# Top.net
KiCad netlist of a schematic drawn in Altium Designer
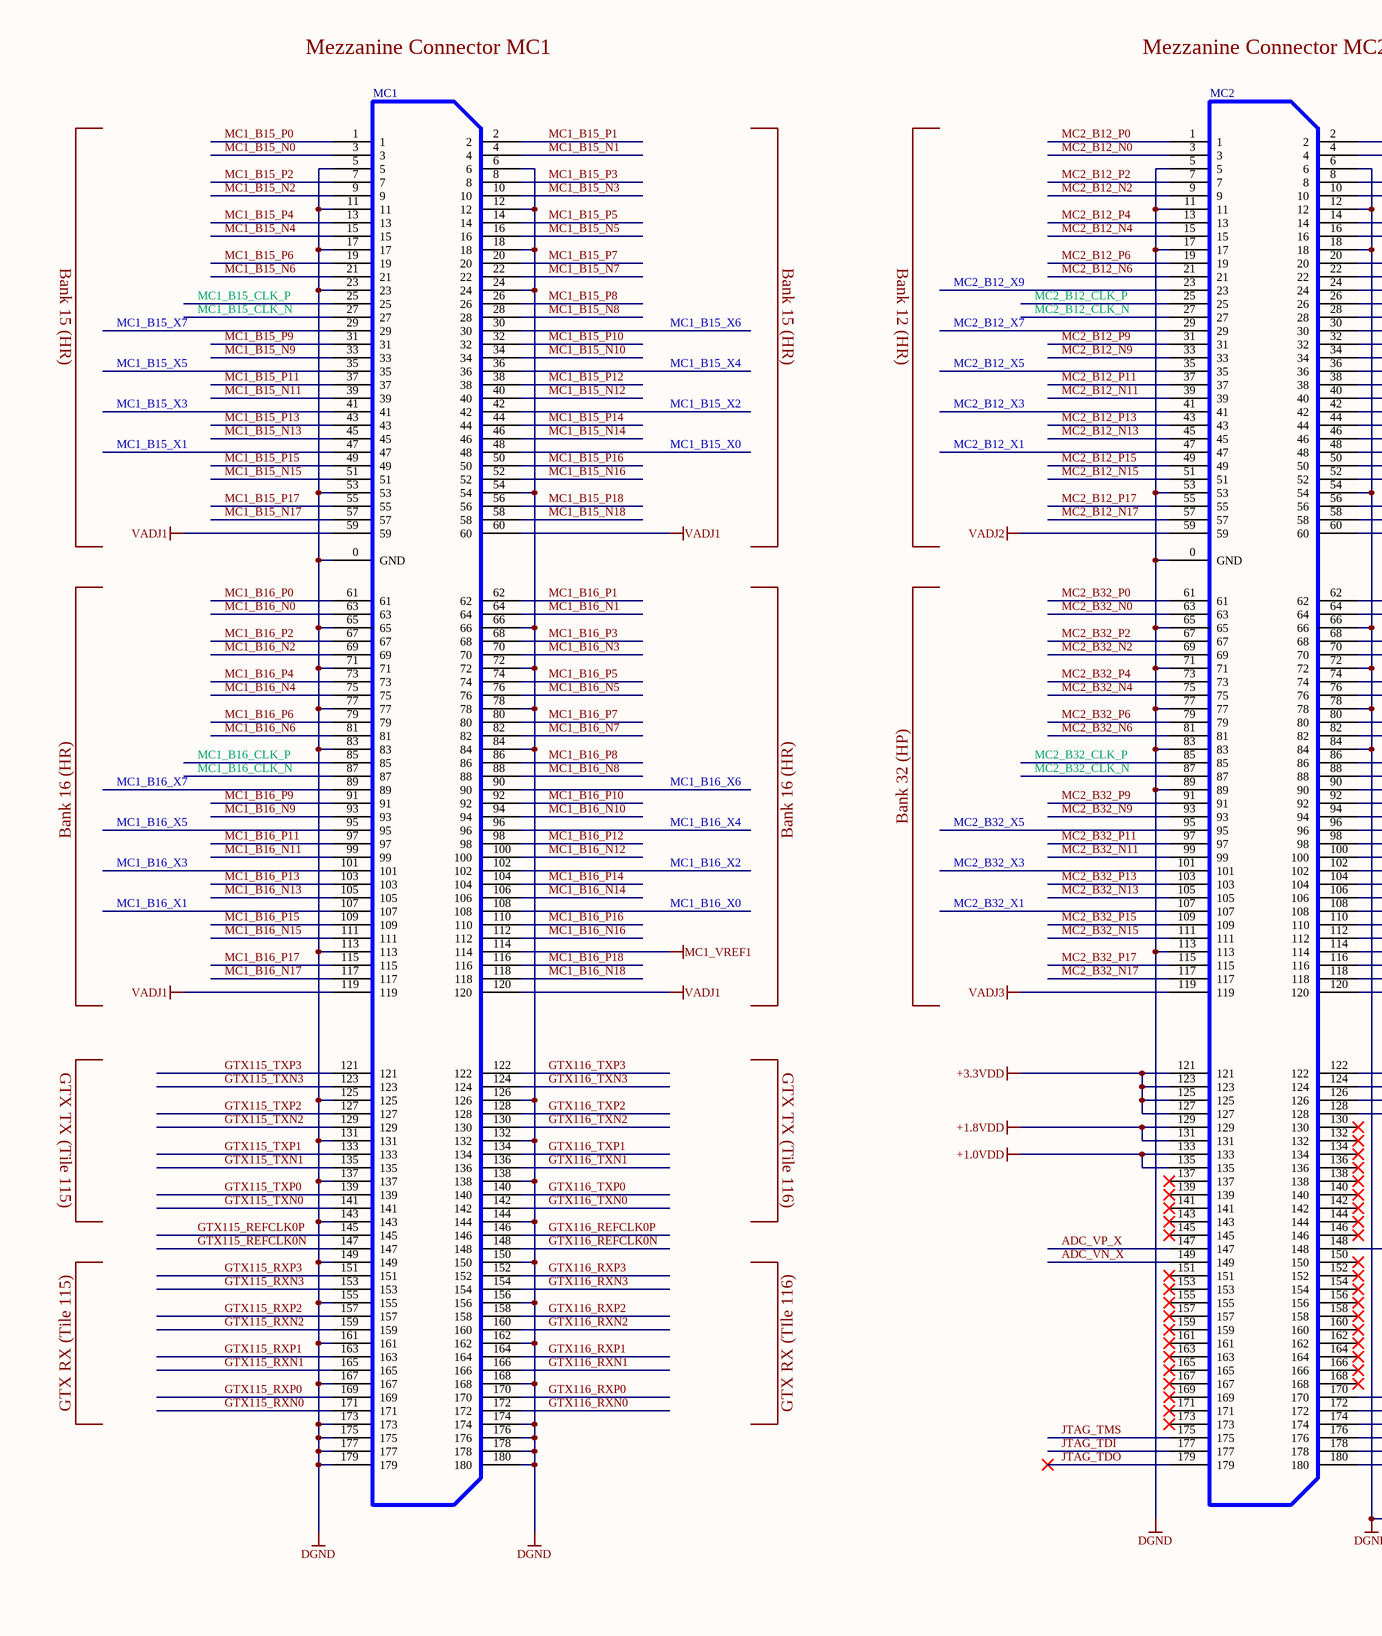
[diagram p0: Top.SchDoc, left]
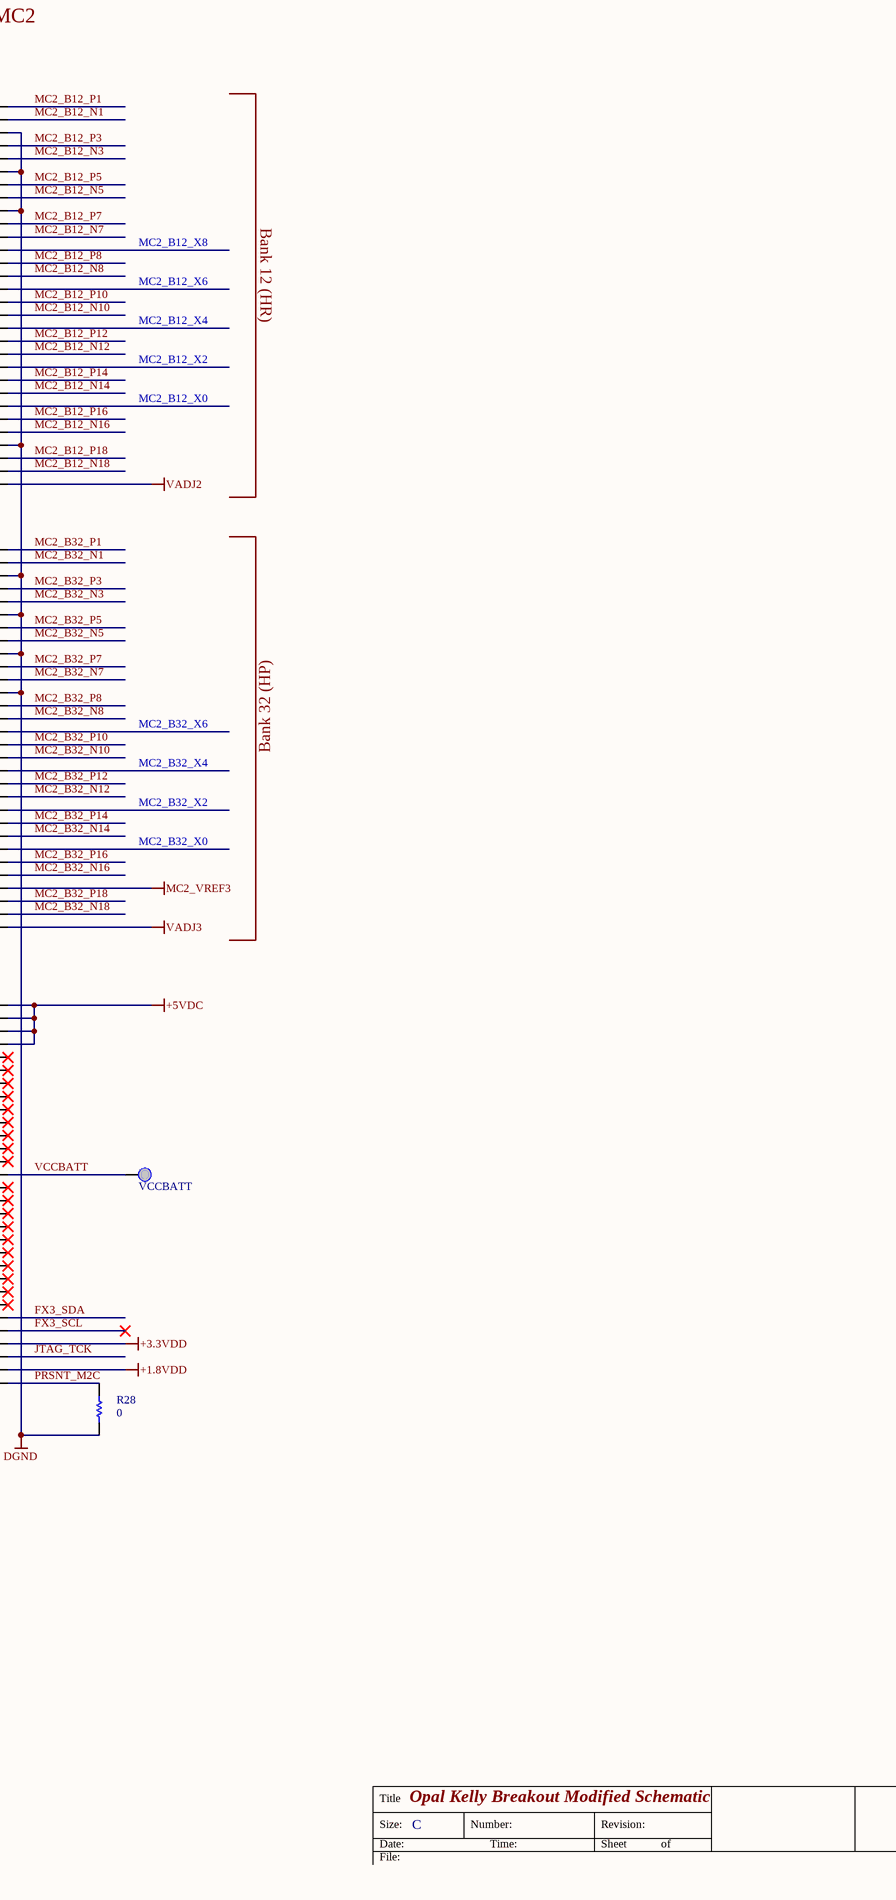
[diagram p1: Top.SchDoc, right]

(export (version "E")
  (design (tool "Eeschema 10.0.6"))
  (components
    (comp (ref "MC1")
      (value "QTH-090-01-F-D-A")
      (footprint "QTH-090-01-X-D")
      (description "0.5mm hi-speed, high-density header (Female)")
      (fields (field (name "MANUFACTURER") "Samtec") (field (name "PARTNUMBER") "000876"))
      (libsource (lib "Aligni") (part "QTH-090"))
    )
    (comp (ref "MC2")
      (value "QTH-090-01-F-D-A")
      (footprint "QTH-090-01-X-D")
      (description "0.5mm hi-speed, high-density header (Female)")
      (fields (field (name "MANUFACTURER") "Samtec") (field (name "PARTNUMBER") "000876"))
      (libsource (lib "Aligni") (part "QTH-090"))
    )
    (comp (ref "R28")
      (value "0")
      (footprint "RESC1608N")
      (description "Zero-ohm resistor")
      (fields (field (name "MANUFACTURER") "Vishay") (field (name "PARTNUMBER") "000411"))
      (libsource (lib "Aligni") (part "Resistor"))
    )
    (comp (ref "TP6")
      (value "VCCBATT")
      (footprint "TP_MED")
      (description "Testpoint")
      (fields (field (name "MANUFACTURER") "Keystone Electronics") (field (name "PARTNUMBER") "000265"))
      (libsource (lib "Aligni") (part "TESTPOINT"))
    )
  )
  (nets
    (net (code "1") (name "+1.0VDD") (class "Default")
      (node (ref "MC2") (pin "133") (pinfunction "133_133") (pintype "passive"))
      (node (ref "MC2") (pin "135") (pinfunction "135_135") (pintype "passive"))
    )
    (net (code "2") (name "+1.8VDD") (class "Default")
      (node (ref "MC2") (pin "129") (pinfunction "129_129") (pintype "passive"))
      (node (ref "MC2") (pin "131") (pinfunction "131_131") (pintype "passive"))
      (node (ref "MC2") (pin "178") (pinfunction "178_178") (pintype "passive"))
    )
    (net (code "3") (name "+3.3VDD") (class "Default")
      (node (ref "MC2") (pin "121") (pinfunction "121_121") (pintype "passive"))
      (node (ref "MC2") (pin "123") (pinfunction "123_123") (pintype "passive"))
      (node (ref "MC2") (pin "125") (pinfunction "125_125") (pintype "passive"))
      (node (ref "MC2") (pin "127") (pinfunction "127_127") (pintype "passive"))
      (node (ref "MC2") (pin "174") (pinfunction "174_174") (pintype "passive"))
    )
    (net (code "4") (name "+5VDC") (class "Default")
      (node (ref "MC2") (pin "122") (pinfunction "122_122") (pintype "passive"))
      (node (ref "MC2") (pin "124") (pinfunction "124_124") (pintype "passive"))
      (node (ref "MC2") (pin "126") (pinfunction "126_126") (pintype "passive"))
      (node (ref "MC2") (pin "128") (pinfunction "128_128") (pintype "passive"))
    )
    (net (code "5") (name "/ADC_VN_X") (class "Default")
      (node (ref "MC2") (pin "149") (pinfunction "149_149") (pintype "passive"))
    )
    (net (code "6") (name "/ADC_VP_X") (class "Default")
      (node (ref "MC2") (pin "147") (pinfunction "147_147") (pintype "passive"))
    )
    (net (code "7") (name "/FX3_SCL") (class "Default")
      (node (ref "MC2") (pin "172") (pinfunction "172_172") (pintype "passive+no_connect"))
    )
    (net (code "8") (name "/FX3_SDA") (class "Default")
      (node (ref "MC2") (pin "170") (pinfunction "170_170") (pintype "passive"))
    )
    (net (code "9") (name "/GTX115_REFCLK0N") (class "Default")
      (node (ref "MC1") (pin "147") (pinfunction "147_147") (pintype "passive"))
    )
    (net (code "10") (name "/GTX115_REFCLK0P") (class "Default")
      (node (ref "MC1") (pin "145") (pinfunction "145_145") (pintype "passive"))
    )
    (net (code "11") (name "/GTX115_RXN0") (class "Default")
      (node (ref "MC1") (pin "171") (pinfunction "171_171") (pintype "passive"))
    )
    (net (code "12") (name "/GTX115_RXN1") (class "Default")
      (node (ref "MC1") (pin "165") (pinfunction "165_165") (pintype "passive"))
    )
    (net (code "13") (name "/GTX115_RXN2") (class "Default")
      (node (ref "MC1") (pin "159") (pinfunction "159_159") (pintype "passive"))
    )
    (net (code "14") (name "/GTX115_RXN3") (class "Default")
      (node (ref "MC1") (pin "153") (pinfunction "153_153") (pintype "passive"))
    )
    (net (code "15") (name "/GTX115_RXP0") (class "Default")
      (node (ref "MC1") (pin "169") (pinfunction "169_169") (pintype "passive"))
    )
    (net (code "16") (name "/GTX115_RXP1") (class "Default")
      (node (ref "MC1") (pin "163") (pinfunction "163_163") (pintype "passive"))
    )
    (net (code "17") (name "/GTX115_RXP2") (class "Default")
      (node (ref "MC1") (pin "157") (pinfunction "157_157") (pintype "passive"))
    )
    (net (code "18") (name "/GTX115_RXP3") (class "Default")
      (node (ref "MC1") (pin "151") (pinfunction "151_151") (pintype "passive"))
    )
    (net (code "19") (name "/GTX115_TXN0") (class "Default")
      (node (ref "MC1") (pin "141") (pinfunction "141_141") (pintype "passive"))
    )
    (net (code "20") (name "/GTX115_TXN1") (class "Default")
      (node (ref "MC1") (pin "135") (pinfunction "135_135") (pintype "passive"))
    )
    (net (code "21") (name "/GTX115_TXN2") (class "Default")
      (node (ref "MC1") (pin "129") (pinfunction "129_129") (pintype "passive"))
    )
    (net (code "22") (name "/GTX115_TXN3") (class "Default")
      (node (ref "MC1") (pin "123") (pinfunction "123_123") (pintype "passive"))
    )
    (net (code "23") (name "/GTX115_TXP0") (class "Default")
      (node (ref "MC1") (pin "139") (pinfunction "139_139") (pintype "passive"))
    )
    (net (code "24") (name "/GTX115_TXP1") (class "Default")
      (node (ref "MC1") (pin "133") (pinfunction "133_133") (pintype "passive"))
    )
    (net (code "25") (name "/GTX115_TXP2") (class "Default")
      (node (ref "MC1") (pin "127") (pinfunction "127_127") (pintype "passive"))
    )
    (net (code "26") (name "/GTX115_TXP3") (class "Default")
      (node (ref "MC1") (pin "121") (pinfunction "121_121") (pintype "passive"))
    )
    (net (code "27") (name "/GTX116_REFCLK0N") (class "Default")
      (node (ref "MC1") (pin "148") (pinfunction "148_148") (pintype "passive"))
    )
    (net (code "28") (name "/GTX116_REFCLK0P") (class "Default")
      (node (ref "MC1") (pin "146") (pinfunction "146_146") (pintype "passive"))
    )
    (net (code "29") (name "/GTX116_RXN0") (class "Default")
      (node (ref "MC1") (pin "172") (pinfunction "172_172") (pintype "passive"))
    )
    (net (code "30") (name "/GTX116_RXN1") (class "Default")
      (node (ref "MC1") (pin "166") (pinfunction "166_166") (pintype "passive"))
    )
    (net (code "31") (name "/GTX116_RXN2") (class "Default")
      (node (ref "MC1") (pin "160") (pinfunction "160_160") (pintype "passive"))
    )
    (net (code "32") (name "/GTX116_RXN3") (class "Default")
      (node (ref "MC1") (pin "154") (pinfunction "154_154") (pintype "passive"))
    )
    (net (code "33") (name "/GTX116_RXP0") (class "Default")
      (node (ref "MC1") (pin "170") (pinfunction "170_170") (pintype "passive"))
    )
    (net (code "34") (name "/GTX116_RXP1") (class "Default")
      (node (ref "MC1") (pin "164") (pinfunction "164_164") (pintype "passive"))
    )
    (net (code "35") (name "/GTX116_RXP2") (class "Default")
      (node (ref "MC1") (pin "158") (pinfunction "158_158") (pintype "passive"))
    )
    (net (code "36") (name "/GTX116_RXP3") (class "Default")
      (node (ref "MC1") (pin "152") (pinfunction "152_152") (pintype "passive"))
    )
    (net (code "37") (name "/GTX116_TXN0") (class "Default")
      (node (ref "MC1") (pin "142") (pinfunction "142_142") (pintype "passive"))
    )
    (net (code "38") (name "/GTX116_TXN1") (class "Default")
      (node (ref "MC1") (pin "136") (pinfunction "136_136") (pintype "passive"))
    )
    (net (code "39") (name "/GTX116_TXN2") (class "Default")
      (node (ref "MC1") (pin "130") (pinfunction "130_130") (pintype "passive"))
    )
    (net (code "40") (name "/GTX116_TXN3") (class "Default")
      (node (ref "MC1") (pin "124") (pinfunction "124_124") (pintype "passive"))
    )
    (net (code "41") (name "/GTX116_TXP0") (class "Default")
      (node (ref "MC1") (pin "140") (pinfunction "140_140") (pintype "passive"))
    )
    (net (code "42") (name "/GTX116_TXP1") (class "Default")
      (node (ref "MC1") (pin "134") (pinfunction "134_134") (pintype "passive"))
    )
    (net (code "43") (name "/GTX116_TXP2") (class "Default")
      (node (ref "MC1") (pin "128") (pinfunction "128_128") (pintype "passive"))
    )
    (net (code "44") (name "/GTX116_TXP3") (class "Default")
      (node (ref "MC1") (pin "122") (pinfunction "122_122") (pintype "passive"))
    )
    (net (code "45") (name "/JTAG_TCK") (class "Default")
      (node (ref "MC2") (pin "176") (pinfunction "176_176") (pintype "passive"))
    )
    (net (code "46") (name "/JTAG_TDI") (class "Default")
      (node (ref "MC2") (pin "177") (pinfunction "177_177") (pintype "passive"))
    )
    (net (code "47") (name "/JTAG_TDO") (class "Default")
      (node (ref "MC2") (pin "179") (pinfunction "179_179") (pintype "passive+no_connect"))
    )
    (net (code "48") (name "/JTAG_TMS") (class "Default")
      (node (ref "MC2") (pin "175") (pinfunction "175_175") (pintype "passive"))
    )
    (net (code "49") (name "/MC1_B15_CLK_N") (class "Default")
      (node (ref "MC1") (pin "27") (pinfunction "27_27") (pintype "passive"))
    )
    (net (code "50") (name "/MC1_B15_CLK_P") (class "Default")
      (node (ref "MC1") (pin "25") (pinfunction "25_25") (pintype "passive"))
    )
    (net (code "51") (name "/MC1_B15_N0") (class "Default")
      (node (ref "MC1") (pin "3") (pinfunction "3_3") (pintype "passive"))
    )
    (net (code "52") (name "/MC1_B15_N1") (class "Default")
      (node (ref "MC1") (pin "4") (pinfunction "4_4") (pintype "passive"))
    )
    (net (code "53") (name "/MC1_B15_N2") (class "Default")
      (node (ref "MC1") (pin "9") (pinfunction "9_9") (pintype "passive"))
    )
    (net (code "54") (name "/MC1_B15_N3") (class "Default")
      (node (ref "MC1") (pin "10") (pinfunction "10_10") (pintype "passive"))
    )
    (net (code "55") (name "/MC1_B15_N4") (class "Default")
      (node (ref "MC1") (pin "15") (pinfunction "15_15") (pintype "passive"))
    )
    (net (code "56") (name "/MC1_B15_N5") (class "Default")
      (node (ref "MC1") (pin "16") (pinfunction "16_16") (pintype "passive"))
    )
    (net (code "57") (name "/MC1_B15_N6") (class "Default")
      (node (ref "MC1") (pin "21") (pinfunction "21_21") (pintype "passive"))
    )
    (net (code "58") (name "/MC1_B15_N7") (class "Default")
      (node (ref "MC1") (pin "22") (pinfunction "22_22") (pintype "passive"))
    )
    (net (code "59") (name "/MC1_B15_N8") (class "Default")
      (node (ref "MC1") (pin "28") (pinfunction "28_28") (pintype "passive"))
    )
    (net (code "60") (name "/MC1_B15_N9") (class "Default")
      (node (ref "MC1") (pin "33") (pinfunction "33_33") (pintype "passive"))
    )
    (net (code "61") (name "/MC1_B15_N10") (class "Default")
      (node (ref "MC1") (pin "34") (pinfunction "34_34") (pintype "passive"))
    )
    (net (code "62") (name "/MC1_B15_N11") (class "Default")
      (node (ref "MC1") (pin "39") (pinfunction "39_39") (pintype "passive"))
    )
    (net (code "63") (name "/MC1_B15_N12") (class "Default")
      (node (ref "MC1") (pin "40") (pinfunction "40_40") (pintype "passive"))
    )
    (net (code "64") (name "/MC1_B15_N13") (class "Default")
      (node (ref "MC1") (pin "45") (pinfunction "45_45") (pintype "passive"))
    )
    (net (code "65") (name "/MC1_B15_N14") (class "Default")
      (node (ref "MC1") (pin "46") (pinfunction "46_46") (pintype "passive"))
    )
    (net (code "66") (name "/MC1_B15_N15") (class "Default")
      (node (ref "MC1") (pin "51") (pinfunction "51_51") (pintype "passive"))
    )
    (net (code "67") (name "/MC1_B15_N16") (class "Default")
      (node (ref "MC1") (pin "52") (pinfunction "52_52") (pintype "passive"))
    )
    (net (code "68") (name "/MC1_B15_N17") (class "Default")
      (node (ref "MC1") (pin "57") (pinfunction "57_57") (pintype "passive"))
    )
    (net (code "69") (name "/MC1_B15_N18") (class "Default")
      (node (ref "MC1") (pin "58") (pinfunction "58_58") (pintype "passive"))
    )
    (net (code "70") (name "/MC1_B15_P0") (class "Default")
      (node (ref "MC1") (pin "1") (pinfunction "1_1") (pintype "passive"))
    )
    (net (code "71") (name "/MC1_B15_P1") (class "Default")
      (node (ref "MC1") (pin "2") (pinfunction "2_2") (pintype "passive"))
    )
    (net (code "72") (name "/MC1_B15_P2") (class "Default")
      (node (ref "MC1") (pin "7") (pinfunction "7_7") (pintype "passive"))
    )
    (net (code "73") (name "/MC1_B15_P3") (class "Default")
      (node (ref "MC1") (pin "8") (pinfunction "8_8") (pintype "passive"))
    )
    (net (code "74") (name "/MC1_B15_P4") (class "Default")
      (node (ref "MC1") (pin "13") (pinfunction "13_13") (pintype "passive"))
    )
    (net (code "75") (name "/MC1_B15_P5") (class "Default")
      (node (ref "MC1") (pin "14") (pinfunction "14_14") (pintype "passive"))
    )
    (net (code "76") (name "/MC1_B15_P6") (class "Default")
      (node (ref "MC1") (pin "19") (pinfunction "19_19") (pintype "passive"))
    )
    (net (code "77") (name "/MC1_B15_P7") (class "Default")
      (node (ref "MC1") (pin "20") (pinfunction "20_20") (pintype "passive"))
    )
    (net (code "78") (name "/MC1_B15_P8") (class "Default")
      (node (ref "MC1") (pin "26") (pinfunction "26_26") (pintype "passive"))
    )
    (net (code "79") (name "/MC1_B15_P9") (class "Default")
      (node (ref "MC1") (pin "31") (pinfunction "31_31") (pintype "passive"))
    )
    (net (code "80") (name "/MC1_B15_P10") (class "Default")
      (node (ref "MC1") (pin "32") (pinfunction "32_32") (pintype "passive"))
    )
    (net (code "81") (name "/MC1_B15_P11") (class "Default")
      (node (ref "MC1") (pin "37") (pinfunction "37_37") (pintype "passive"))
    )
    (net (code "82") (name "/MC1_B15_P12") (class "Default")
      (node (ref "MC1") (pin "38") (pinfunction "38_38") (pintype "passive"))
    )
    (net (code "83") (name "/MC1_B15_P13") (class "Default")
      (node (ref "MC1") (pin "43") (pinfunction "43_43") (pintype "passive"))
    )
    (net (code "84") (name "/MC1_B15_P14") (class "Default")
      (node (ref "MC1") (pin "44") (pinfunction "44_44") (pintype "passive"))
    )
    (net (code "85") (name "/MC1_B15_P15") (class "Default")
      (node (ref "MC1") (pin "49") (pinfunction "49_49") (pintype "passive"))
    )
    (net (code "86") (name "/MC1_B15_P16") (class "Default")
      (node (ref "MC1") (pin "50") (pinfunction "50_50") (pintype "passive"))
    )
    (net (code "87") (name "/MC1_B15_P17") (class "Default")
      (node (ref "MC1") (pin "55") (pinfunction "55_55") (pintype "passive"))
    )
    (net (code "88") (name "/MC1_B15_P18") (class "Default")
      (node (ref "MC1") (pin "56") (pinfunction "56_56") (pintype "passive"))
    )
    (net (code "89") (name "/MC1_B15_X0") (class "Default")
      (node (ref "MC1") (pin "48") (pinfunction "48_48") (pintype "passive"))
    )
    (net (code "90") (name "/MC1_B15_X1") (class "Default")
      (node (ref "MC1") (pin "47") (pinfunction "47_47") (pintype "passive"))
    )
    (net (code "91") (name "/MC1_B15_X2") (class "Default")
      (node (ref "MC1") (pin "42") (pinfunction "42_42") (pintype "passive"))
    )
    (net (code "92") (name "/MC1_B15_X3") (class "Default")
      (node (ref "MC1") (pin "41") (pinfunction "41_41") (pintype "passive"))
    )
    (net (code "93") (name "/MC1_B15_X4") (class "Default")
      (node (ref "MC1") (pin "36") (pinfunction "36_36") (pintype "passive"))
    )
    (net (code "94") (name "/MC1_B15_X5") (class "Default")
      (node (ref "MC1") (pin "35") (pinfunction "35_35") (pintype "passive"))
    )
    (net (code "95") (name "/MC1_B15_X6") (class "Default")
      (node (ref "MC1") (pin "30") (pinfunction "30_30") (pintype "passive"))
    )
    (net (code "96") (name "/MC1_B15_X7") (class "Default")
      (node (ref "MC1") (pin "29") (pinfunction "29_29") (pintype "passive"))
    )
    (net (code "97") (name "/MC1_B16_CLK_N") (class "Default")
      (node (ref "MC1") (pin "87") (pinfunction "87_87") (pintype "passive"))
    )
    (net (code "98") (name "/MC1_B16_CLK_P") (class "Default")
      (node (ref "MC1") (pin "85") (pinfunction "85_85") (pintype "passive"))
    )
    (net (code "99") (name "/MC1_B16_N0") (class "Default")
      (node (ref "MC1") (pin "63") (pinfunction "63_63") (pintype "passive"))
    )
    (net (code "100") (name "/MC1_B16_N1") (class "Default")
      (node (ref "MC1") (pin "64") (pinfunction "64_64") (pintype "passive"))
    )
    (net (code "101") (name "/MC1_B16_N2") (class "Default")
      (node (ref "MC1") (pin "69") (pinfunction "69_69") (pintype "passive"))
    )
    (net (code "102") (name "/MC1_B16_N3") (class "Default")
      (node (ref "MC1") (pin "70") (pinfunction "70_70") (pintype "passive"))
    )
    (net (code "103") (name "/MC1_B16_N4") (class "Default")
      (node (ref "MC1") (pin "75") (pinfunction "75_75") (pintype "passive"))
    )
    (net (code "104") (name "/MC1_B16_N5") (class "Default")
      (node (ref "MC1") (pin "76") (pinfunction "76_76") (pintype "passive"))
    )
    (net (code "105") (name "/MC1_B16_N6") (class "Default")
      (node (ref "MC1") (pin "81") (pinfunction "81_81") (pintype "passive"))
    )
    (net (code "106") (name "/MC1_B16_N7") (class "Default")
      (node (ref "MC1") (pin "82") (pinfunction "82_82") (pintype "passive"))
    )
    (net (code "107") (name "/MC1_B16_N8") (class "Default")
      (node (ref "MC1") (pin "88") (pinfunction "88_88") (pintype "passive"))
    )
    (net (code "108") (name "/MC1_B16_N9") (class "Default")
      (node (ref "MC1") (pin "93") (pinfunction "93_93") (pintype "passive"))
    )
    (net (code "109") (name "/MC1_B16_N10") (class "Default")
      (node (ref "MC1") (pin "94") (pinfunction "94_94") (pintype "passive"))
    )
    (net (code "110") (name "/MC1_B16_N11") (class "Default")
      (node (ref "MC1") (pin "99") (pinfunction "99_99") (pintype "passive"))
    )
    (net (code "111") (name "/MC1_B16_N12") (class "Default")
      (node (ref "MC1") (pin "100") (pinfunction "100_100") (pintype "passive"))
    )
    (net (code "112") (name "/MC1_B16_N13") (class "Default")
      (node (ref "MC1") (pin "105") (pinfunction "105_105") (pintype "passive"))
    )
    (net (code "113") (name "/MC1_B16_N14") (class "Default")
      (node (ref "MC1") (pin "106") (pinfunction "106_106") (pintype "passive"))
    )
    (net (code "114") (name "/MC1_B16_N15") (class "Default")
      (node (ref "MC1") (pin "111") (pinfunction "111_111") (pintype "passive"))
    )
    (net (code "115") (name "/MC1_B16_N16") (class "Default")
      (node (ref "MC1") (pin "112") (pinfunction "112_112") (pintype "passive"))
    )
    (net (code "116") (name "/MC1_B16_N17") (class "Default")
      (node (ref "MC1") (pin "117") (pinfunction "117_117") (pintype "passive"))
    )
    (net (code "117") (name "/MC1_B16_N18") (class "Default")
      (node (ref "MC1") (pin "118") (pinfunction "118_118") (pintype "passive"))
    )
    (net (code "118") (name "/MC1_B16_P0") (class "Default")
      (node (ref "MC1") (pin "61") (pinfunction "61_61") (pintype "passive"))
    )
    (net (code "119") (name "/MC1_B16_P1") (class "Default")
      (node (ref "MC1") (pin "62") (pinfunction "62_62") (pintype "passive"))
    )
    (net (code "120") (name "/MC1_B16_P2") (class "Default")
      (node (ref "MC1") (pin "67") (pinfunction "67_67") (pintype "passive"))
    )
    (net (code "121") (name "/MC1_B16_P3") (class "Default")
      (node (ref "MC1") (pin "68") (pinfunction "68_68") (pintype "passive"))
    )
    (net (code "122") (name "/MC1_B16_P4") (class "Default")
      (node (ref "MC1") (pin "73") (pinfunction "73_73") (pintype "passive"))
    )
    (net (code "123") (name "/MC1_B16_P5") (class "Default")
      (node (ref "MC1") (pin "74") (pinfunction "74_74") (pintype "passive"))
    )
    (net (code "124") (name "/MC1_B16_P6") (class "Default")
      (node (ref "MC1") (pin "79") (pinfunction "79_79") (pintype "passive"))
    )
    (net (code "125") (name "/MC1_B16_P7") (class "Default")
      (node (ref "MC1") (pin "80") (pinfunction "80_80") (pintype "passive"))
    )
    (net (code "126") (name "/MC1_B16_P8") (class "Default")
      (node (ref "MC1") (pin "86") (pinfunction "86_86") (pintype "passive"))
    )
    (net (code "127") (name "/MC1_B16_P9") (class "Default")
      (node (ref "MC1") (pin "91") (pinfunction "91_91") (pintype "passive"))
    )
    (net (code "128") (name "/MC1_B16_P10") (class "Default")
      (node (ref "MC1") (pin "92") (pinfunction "92_92") (pintype "passive"))
    )
    (net (code "129") (name "/MC1_B16_P11") (class "Default")
      (node (ref "MC1") (pin "97") (pinfunction "97_97") (pintype "passive"))
    )
    (net (code "130") (name "/MC1_B16_P12") (class "Default")
      (node (ref "MC1") (pin "98") (pinfunction "98_98") (pintype "passive"))
    )
    (net (code "131") (name "/MC1_B16_P13") (class "Default")
      (node (ref "MC1") (pin "103") (pinfunction "103_103") (pintype "passive"))
    )
    (net (code "132") (name "/MC1_B16_P14") (class "Default")
      (node (ref "MC1") (pin "104") (pinfunction "104_104") (pintype "passive"))
    )
    (net (code "133") (name "/MC1_B16_P15") (class "Default")
      (node (ref "MC1") (pin "109") (pinfunction "109_109") (pintype "passive"))
    )
    (net (code "134") (name "/MC1_B16_P16") (class "Default")
      (node (ref "MC1") (pin "110") (pinfunction "110_110") (pintype "passive"))
    )
    (net (code "135") (name "/MC1_B16_P17") (class "Default")
      (node (ref "MC1") (pin "115") (pinfunction "115_115") (pintype "passive"))
    )
    (net (code "136") (name "/MC1_B16_P18") (class "Default")
      (node (ref "MC1") (pin "116") (pinfunction "116_116") (pintype "passive"))
    )
    (net (code "137") (name "/MC1_B16_X0") (class "Default")
      (node (ref "MC1") (pin "108") (pinfunction "108_108") (pintype "passive"))
    )
    (net (code "138") (name "/MC1_B16_X1") (class "Default")
      (node (ref "MC1") (pin "107") (pinfunction "107_107") (pintype "passive"))
    )
    (net (code "139") (name "/MC1_B16_X2") (class "Default")
      (node (ref "MC1") (pin "102") (pinfunction "102_102") (pintype "passive"))
    )
    (net (code "140") (name "/MC1_B16_X3") (class "Default")
      (node (ref "MC1") (pin "101") (pinfunction "101_101") (pintype "passive"))
    )
    (net (code "141") (name "/MC1_B16_X4") (class "Default")
      (node (ref "MC1") (pin "96") (pinfunction "96_96") (pintype "passive"))
    )
    (net (code "142") (name "/MC1_B16_X5") (class "Default")
      (node (ref "MC1") (pin "95") (pinfunction "95_95") (pintype "passive"))
    )
    (net (code "143") (name "/MC1_B16_X6") (class "Default")
      (node (ref "MC1") (pin "90") (pinfunction "90_90") (pintype "passive"))
    )
    (net (code "144") (name "/MC1_B16_X7") (class "Default")
      (node (ref "MC1") (pin "89") (pinfunction "89_89") (pintype "passive"))
    )
    (net (code "145") (name "/MC2_B12_CLK_N") (class "Default")
      (node (ref "MC2") (pin "27") (pinfunction "27_27") (pintype "passive"))
    )
    (net (code "146") (name "/MC2_B12_CLK_P") (class "Default")
      (node (ref "MC2") (pin "25") (pinfunction "25_25") (pintype "passive"))
    )
    (net (code "147") (name "/MC2_B12_N0") (class "Default")
      (node (ref "MC2") (pin "3") (pinfunction "3_3") (pintype "passive"))
    )
    (net (code "148") (name "/MC2_B12_N1") (class "Default")
      (node (ref "MC2") (pin "4") (pinfunction "4_4") (pintype "passive"))
    )
    (net (code "149") (name "/MC2_B12_N2") (class "Default")
      (node (ref "MC2") (pin "9") (pinfunction "9_9") (pintype "passive"))
    )
    (net (code "150") (name "/MC2_B12_N3") (class "Default")
      (node (ref "MC2") (pin "10") (pinfunction "10_10") (pintype "passive"))
    )
    (net (code "151") (name "/MC2_B12_N4") (class "Default")
      (node (ref "MC2") (pin "15") (pinfunction "15_15") (pintype "passive"))
    )
    (net (code "152") (name "/MC2_B12_N5") (class "Default")
      (node (ref "MC2") (pin "16") (pinfunction "16_16") (pintype "passive"))
    )
    (net (code "153") (name "/MC2_B12_N6") (class "Default")
      (node (ref "MC2") (pin "21") (pinfunction "21_21") (pintype "passive"))
    )
    (net (code "154") (name "/MC2_B12_N7") (class "Default")
      (node (ref "MC2") (pin "22") (pinfunction "22_22") (pintype "passive"))
    )
    (net (code "155") (name "/MC2_B12_N8") (class "Default")
      (node (ref "MC2") (pin "28") (pinfunction "28_28") (pintype "passive"))
    )
    (net (code "156") (name "/MC2_B12_N9") (class "Default")
      (node (ref "MC2") (pin "33") (pinfunction "33_33") (pintype "passive"))
    )
    (net (code "157") (name "/MC2_B12_N10") (class "Default")
      (node (ref "MC2") (pin "34") (pinfunction "34_34") (pintype "passive"))
    )
    (net (code "158") (name "/MC2_B12_N11") (class "Default")
      (node (ref "MC2") (pin "39") (pinfunction "39_39") (pintype "passive"))
    )
    (net (code "159") (name "/MC2_B12_N12") (class "Default")
      (node (ref "MC2") (pin "40") (pinfunction "40_40") (pintype "passive"))
    )
    (net (code "160") (name "/MC2_B12_N13") (class "Default")
      (node (ref "MC2") (pin "45") (pinfunction "45_45") (pintype "passive"))
    )
    (net (code "161") (name "/MC2_B12_N14") (class "Default")
      (node (ref "MC2") (pin "46") (pinfunction "46_46") (pintype "passive"))
    )
    (net (code "162") (name "/MC2_B12_N15") (class "Default")
      (node (ref "MC2") (pin "51") (pinfunction "51_51") (pintype "passive"))
    )
    (net (code "163") (name "/MC2_B12_N16") (class "Default")
      (node (ref "MC2") (pin "52") (pinfunction "52_52") (pintype "passive"))
    )
    (net (code "164") (name "/MC2_B12_N17") (class "Default")
      (node (ref "MC2") (pin "57") (pinfunction "57_57") (pintype "passive"))
    )
    (net (code "165") (name "/MC2_B12_N18") (class "Default")
      (node (ref "MC2") (pin "58") (pinfunction "58_58") (pintype "passive"))
    )
    (net (code "166") (name "/MC2_B12_P0") (class "Default")
      (node (ref "MC2") (pin "1") (pinfunction "1_1") (pintype "passive"))
    )
    (net (code "167") (name "/MC2_B12_P1") (class "Default")
      (node (ref "MC2") (pin "2") (pinfunction "2_2") (pintype "passive"))
    )
    (net (code "168") (name "/MC2_B12_P2") (class "Default")
      (node (ref "MC2") (pin "7") (pinfunction "7_7") (pintype "passive"))
    )
    (net (code "169") (name "/MC2_B12_P3") (class "Default")
      (node (ref "MC2") (pin "8") (pinfunction "8_8") (pintype "passive"))
    )
    (net (code "170") (name "/MC2_B12_P4") (class "Default")
      (node (ref "MC2") (pin "13") (pinfunction "13_13") (pintype "passive"))
    )
    (net (code "171") (name "/MC2_B12_P5") (class "Default")
      (node (ref "MC2") (pin "14") (pinfunction "14_14") (pintype "passive"))
    )
    (net (code "172") (name "/MC2_B12_P6") (class "Default")
      (node (ref "MC2") (pin "19") (pinfunction "19_19") (pintype "passive"))
    )
    (net (code "173") (name "/MC2_B12_P7") (class "Default")
      (node (ref "MC2") (pin "20") (pinfunction "20_20") (pintype "passive"))
    )
    (net (code "174") (name "/MC2_B12_P8") (class "Default")
      (node (ref "MC2") (pin "26") (pinfunction "26_26") (pintype "passive"))
    )
    (net (code "175") (name "/MC2_B12_P9") (class "Default")
      (node (ref "MC2") (pin "31") (pinfunction "31_31") (pintype "passive"))
    )
    (net (code "176") (name "/MC2_B12_P10") (class "Default")
      (node (ref "MC2") (pin "32") (pinfunction "32_32") (pintype "passive"))
    )
    (net (code "177") (name "/MC2_B12_P11") (class "Default")
      (node (ref "MC2") (pin "37") (pinfunction "37_37") (pintype "passive"))
    )
    (net (code "178") (name "/MC2_B12_P12") (class "Default")
      (node (ref "MC2") (pin "38") (pinfunction "38_38") (pintype "passive"))
    )
    (net (code "179") (name "/MC2_B12_P13") (class "Default")
      (node (ref "MC2") (pin "43") (pinfunction "43_43") (pintype "passive"))
    )
    (net (code "180") (name "/MC2_B12_P14") (class "Default")
      (node (ref "MC2") (pin "44") (pinfunction "44_44") (pintype "passive"))
    )
    (net (code "181") (name "/MC2_B12_P15") (class "Default")
      (node (ref "MC2") (pin "49") (pinfunction "49_49") (pintype "passive"))
    )
    (net (code "182") (name "/MC2_B12_P16") (class "Default")
      (node (ref "MC2") (pin "50") (pinfunction "50_50") (pintype "passive"))
    )
    (net (code "183") (name "/MC2_B12_P17") (class "Default")
      (node (ref "MC2") (pin "55") (pinfunction "55_55") (pintype "passive"))
    )
    (net (code "184") (name "/MC2_B12_P18") (class "Default")
      (node (ref "MC2") (pin "56") (pinfunction "56_56") (pintype "passive"))
    )
    (net (code "185") (name "/MC2_B12_X0") (class "Default")
      (node (ref "MC2") (pin "48") (pinfunction "48_48") (pintype "passive"))
    )
    (net (code "186") (name "/MC2_B12_X1") (class "Default")
      (node (ref "MC2") (pin "47") (pinfunction "47_47") (pintype "passive"))
    )
    (net (code "187") (name "/MC2_B12_X2") (class "Default")
      (node (ref "MC2") (pin "42") (pinfunction "42_42") (pintype "passive"))
    )
    (net (code "188") (name "/MC2_B12_X3") (class "Default")
      (node (ref "MC2") (pin "41") (pinfunction "41_41") (pintype "passive"))
    )
    (net (code "189") (name "/MC2_B12_X4") (class "Default")
      (node (ref "MC2") (pin "36") (pinfunction "36_36") (pintype "passive"))
    )
    (net (code "190") (name "/MC2_B12_X5") (class "Default")
      (node (ref "MC2") (pin "35") (pinfunction "35_35") (pintype "passive"))
    )
    (net (code "191") (name "/MC2_B12_X6") (class "Default")
      (node (ref "MC2") (pin "30") (pinfunction "30_30") (pintype "passive"))
    )
    (net (code "192") (name "/MC2_B12_X7") (class "Default")
      (node (ref "MC2") (pin "29") (pinfunction "29_29") (pintype "passive"))
    )
    (net (code "193") (name "/MC2_B12_X8") (class "Default")
      (node (ref "MC2") (pin "24") (pinfunction "24_24") (pintype "passive"))
    )
    (net (code "194") (name "/MC2_B12_X9") (class "Default")
      (node (ref "MC2") (pin "23") (pinfunction "23_23") (pintype "passive"))
    )
    (net (code "195") (name "/MC2_B32_CLK_N") (class "Default")
      (node (ref "MC2") (pin "87") (pinfunction "87_87") (pintype "passive"))
    )
    (net (code "196") (name "/MC2_B32_CLK_P") (class "Default")
      (node (ref "MC2") (pin "85") (pinfunction "85_85") (pintype "passive"))
    )
    (net (code "197") (name "/MC2_B32_N0") (class "Default")
      (node (ref "MC2") (pin "63") (pinfunction "63_63") (pintype "passive"))
    )
    (net (code "198") (name "/MC2_B32_N1") (class "Default")
      (node (ref "MC2") (pin "64") (pinfunction "64_64") (pintype "passive"))
    )
    (net (code "199") (name "/MC2_B32_N2") (class "Default")
      (node (ref "MC2") (pin "69") (pinfunction "69_69") (pintype "passive"))
    )
    (net (code "200") (name "/MC2_B32_N3") (class "Default")
      (node (ref "MC2") (pin "70") (pinfunction "70_70") (pintype "passive"))
    )
    (net (code "201") (name "/MC2_B32_N4") (class "Default")
      (node (ref "MC2") (pin "75") (pinfunction "75_75") (pintype "passive"))
    )
    (net (code "202") (name "/MC2_B32_N5") (class "Default")
      (node (ref "MC2") (pin "76") (pinfunction "76_76") (pintype "passive"))
    )
    (net (code "203") (name "/MC2_B32_N6") (class "Default")
      (node (ref "MC2") (pin "81") (pinfunction "81_81") (pintype "passive"))
    )
    (net (code "204") (name "/MC2_B32_N7") (class "Default")
      (node (ref "MC2") (pin "82") (pinfunction "82_82") (pintype "passive"))
    )
    (net (code "205") (name "/MC2_B32_N8") (class "Default")
      (node (ref "MC2") (pin "88") (pinfunction "88_88") (pintype "passive"))
    )
    (net (code "206") (name "/MC2_B32_N9") (class "Default")
      (node (ref "MC2") (pin "93") (pinfunction "93_93") (pintype "passive"))
    )
    (net (code "207") (name "/MC2_B32_N10") (class "Default")
      (node (ref "MC2") (pin "94") (pinfunction "94_94") (pintype "passive"))
    )
    (net (code "208") (name "/MC2_B32_N11") (class "Default")
      (node (ref "MC2") (pin "99") (pinfunction "99_99") (pintype "passive"))
    )
    (net (code "209") (name "/MC2_B32_N12") (class "Default")
      (node (ref "MC2") (pin "100") (pinfunction "100_100") (pintype "passive"))
    )
    (net (code "210") (name "/MC2_B32_N13") (class "Default")
      (node (ref "MC2") (pin "105") (pinfunction "105_105") (pintype "passive"))
    )
    (net (code "211") (name "/MC2_B32_N14") (class "Default")
      (node (ref "MC2") (pin "106") (pinfunction "106_106") (pintype "passive"))
    )
    (net (code "212") (name "/MC2_B32_N15") (class "Default")
      (node (ref "MC2") (pin "111") (pinfunction "111_111") (pintype "passive"))
    )
    (net (code "213") (name "/MC2_B32_N16") (class "Default")
      (node (ref "MC2") (pin "112") (pinfunction "112_112") (pintype "passive"))
    )
    (net (code "214") (name "/MC2_B32_N17") (class "Default")
      (node (ref "MC2") (pin "117") (pinfunction "117_117") (pintype "passive"))
    )
    (net (code "215") (name "/MC2_B32_N18") (class "Default")
      (node (ref "MC2") (pin "118") (pinfunction "118_118") (pintype "passive"))
    )
    (net (code "216") (name "/MC2_B32_P0") (class "Default")
      (node (ref "MC2") (pin "61") (pinfunction "61_61") (pintype "passive"))
    )
    (net (code "217") (name "/MC2_B32_P1") (class "Default")
      (node (ref "MC2") (pin "62") (pinfunction "62_62") (pintype "passive"))
    )
    (net (code "218") (name "/MC2_B32_P2") (class "Default")
      (node (ref "MC2") (pin "67") (pinfunction "67_67") (pintype "passive"))
    )
    (net (code "219") (name "/MC2_B32_P3") (class "Default")
      (node (ref "MC2") (pin "68") (pinfunction "68_68") (pintype "passive"))
    )
    (net (code "220") (name "/MC2_B32_P4") (class "Default")
      (node (ref "MC2") (pin "73") (pinfunction "73_73") (pintype "passive"))
    )
    (net (code "221") (name "/MC2_B32_P5") (class "Default")
      (node (ref "MC2") (pin "74") (pinfunction "74_74") (pintype "passive"))
    )
    (net (code "222") (name "/MC2_B32_P6") (class "Default")
      (node (ref "MC2") (pin "79") (pinfunction "79_79") (pintype "passive"))
    )
    (net (code "223") (name "/MC2_B32_P7") (class "Default")
      (node (ref "MC2") (pin "80") (pinfunction "80_80") (pintype "passive"))
    )
    (net (code "224") (name "/MC2_B32_P8") (class "Default")
      (node (ref "MC2") (pin "86") (pinfunction "86_86") (pintype "passive"))
    )
    (net (code "225") (name "/MC2_B32_P9") (class "Default")
      (node (ref "MC2") (pin "91") (pinfunction "91_91") (pintype "passive"))
    )
    (net (code "226") (name "/MC2_B32_P10") (class "Default")
      (node (ref "MC2") (pin "92") (pinfunction "92_92") (pintype "passive"))
    )
    (net (code "227") (name "/MC2_B32_P11") (class "Default")
      (node (ref "MC2") (pin "97") (pinfunction "97_97") (pintype "passive"))
    )
    (net (code "228") (name "/MC2_B32_P12") (class "Default")
      (node (ref "MC2") (pin "98") (pinfunction "98_98") (pintype "passive"))
    )
    (net (code "229") (name "/MC2_B32_P13") (class "Default")
      (node (ref "MC2") (pin "103") (pinfunction "103_103") (pintype "passive"))
    )
    (net (code "230") (name "/MC2_B32_P14") (class "Default")
      (node (ref "MC2") (pin "104") (pinfunction "104_104") (pintype "passive"))
    )
    (net (code "231") (name "/MC2_B32_P15") (class "Default")
      (node (ref "MC2") (pin "109") (pinfunction "109_109") (pintype "passive"))
    )
    (net (code "232") (name "/MC2_B32_P16") (class "Default")
      (node (ref "MC2") (pin "110") (pinfunction "110_110") (pintype "passive"))
    )
    (net (code "233") (name "/MC2_B32_P17") (class "Default")
      (node (ref "MC2") (pin "115") (pinfunction "115_115") (pintype "passive"))
    )
    (net (code "234") (name "/MC2_B32_P18") (class "Default")
      (node (ref "MC2") (pin "116") (pinfunction "116_116") (pintype "passive"))
    )
    (net (code "235") (name "/MC2_B32_X0") (class "Default")
      (node (ref "MC2") (pin "108") (pinfunction "108_108") (pintype "passive"))
    )
    (net (code "236") (name "/MC2_B32_X1") (class "Default")
      (node (ref "MC2") (pin "107") (pinfunction "107_107") (pintype "passive"))
    )
    (net (code "237") (name "/MC2_B32_X2") (class "Default")
      (node (ref "MC2") (pin "102") (pinfunction "102_102") (pintype "passive"))
    )
    (net (code "238") (name "/MC2_B32_X3") (class "Default")
      (node (ref "MC2") (pin "101") (pinfunction "101_101") (pintype "passive"))
    )
    (net (code "239") (name "/MC2_B32_X4") (class "Default")
      (node (ref "MC2") (pin "96") (pinfunction "96_96") (pintype "passive"))
    )
    (net (code "240") (name "/MC2_B32_X5") (class "Default")
      (node (ref "MC2") (pin "95") (pinfunction "95_95") (pintype "passive"))
    )
    (net (code "241") (name "/MC2_B32_X6") (class "Default")
      (node (ref "MC2") (pin "90") (pinfunction "90_90") (pintype "passive"))
    )
    (net (code "242") (name "/PRSNT_M2C") (class "Default")
      (node (ref "MC2") (pin "180") (pinfunction "180_180") (pintype "passive"))
      (node (ref "R28") (pin "2") (pinfunction "2_2") (pintype "passive"))
    )
    (net (code "243") (name "/VCCBATT") (class "Default")
      (node (ref "MC2") (pin "148") (pinfunction "148_148") (pintype "passive"))
      (node (ref "TP6") (pin "1") (pinfunction "PIN_1") (pintype "passive"))
    )
    (net (code "244") (name "DGND") (class "Default")
      (node (ref "MC1") (pin "0") (pinfunction "GND_0") (pintype "power_in"))
      (node (ref "MC1") (pin "11") (pinfunction "11_11") (pintype "passive"))
      (node (ref "MC1") (pin "113") (pinfunction "113_113") (pintype "passive"))
      (node (ref "MC1") (pin "12") (pinfunction "12_12") (pintype "passive"))
      (node (ref "MC1") (pin "125") (pinfunction "125_125") (pintype "passive"))
      (node (ref "MC1") (pin "126") (pinfunction "126_126") (pintype "passive"))
      (node (ref "MC1") (pin "131") (pinfunction "131_131") (pintype "passive"))
      (node (ref "MC1") (pin "132") (pinfunction "132_132") (pintype "passive"))
      (node (ref "MC1") (pin "137") (pinfunction "137_137") (pintype "passive"))
      (node (ref "MC1") (pin "138") (pinfunction "138_138") (pintype "passive"))
      (node (ref "MC1") (pin "143") (pinfunction "143_143") (pintype "passive"))
      (node (ref "MC1") (pin "144") (pinfunction "144_144") (pintype "passive"))
      (node (ref "MC1") (pin "149") (pinfunction "149_149") (pintype "passive"))
      (node (ref "MC1") (pin "150") (pinfunction "150_150") (pintype "passive"))
      (node (ref "MC1") (pin "155") (pinfunction "155_155") (pintype "passive"))
      (node (ref "MC1") (pin "156") (pinfunction "156_156") (pintype "passive"))
      (node (ref "MC1") (pin "161") (pinfunction "161_161") (pintype "passive"))
      (node (ref "MC1") (pin "162") (pinfunction "162_162") (pintype "passive"))
      (node (ref "MC1") (pin "167") (pinfunction "167_167") (pintype "passive"))
      (node (ref "MC1") (pin "168") (pinfunction "168_168") (pintype "passive"))
      (node (ref "MC1") (pin "17") (pinfunction "17_17") (pintype "passive"))
      (node (ref "MC1") (pin "173") (pinfunction "173_173") (pintype "passive"))
      (node (ref "MC1") (pin "174") (pinfunction "174_174") (pintype "passive"))
      (node (ref "MC1") (pin "175") (pinfunction "175_175") (pintype "passive"))
      (node (ref "MC1") (pin "176") (pinfunction "176_176") (pintype "passive"))
      (node (ref "MC1") (pin "177") (pinfunction "177_177") (pintype "passive"))
      (node (ref "MC1") (pin "178") (pinfunction "178_178") (pintype "passive"))
      (node (ref "MC1") (pin "179") (pinfunction "179_179") (pintype "passive"))
      (node (ref "MC1") (pin "18") (pinfunction "18_18") (pintype "passive"))
      (node (ref "MC1") (pin "180") (pinfunction "180_180") (pintype "passive"))
      (node (ref "MC1") (pin "23") (pinfunction "23_23") (pintype "passive"))
      (node (ref "MC1") (pin "24") (pinfunction "24_24") (pintype "passive"))
      (node (ref "MC1") (pin "5") (pinfunction "5_5") (pintype "passive"))
      (node (ref "MC1") (pin "53") (pinfunction "53_53") (pintype "passive"))
      (node (ref "MC1") (pin "54") (pinfunction "54_54") (pintype "passive"))
      (node (ref "MC1") (pin "6") (pinfunction "6_6") (pintype "passive"))
      (node (ref "MC1") (pin "65") (pinfunction "65_65") (pintype "passive"))
      (node (ref "MC1") (pin "66") (pinfunction "66_66") (pintype "passive"))
      (node (ref "MC1") (pin "71") (pinfunction "71_71") (pintype "passive"))
      (node (ref "MC1") (pin "72") (pinfunction "72_72") (pintype "passive"))
      (node (ref "MC1") (pin "77") (pinfunction "77_77") (pintype "passive"))
      (node (ref "MC1") (pin "78") (pinfunction "78_78") (pintype "passive"))
      (node (ref "MC1") (pin "83") (pinfunction "83_83") (pintype "passive"))
      (node (ref "MC1") (pin "84") (pinfunction "84_84") (pintype "passive"))
      (node (ref "MC2") (pin "0") (pinfunction "GND_0") (pintype "power_in"))
      (node (ref "MC2") (pin "11") (pinfunction "11_11") (pintype "passive"))
      (node (ref "MC2") (pin "113") (pinfunction "113_113") (pintype "passive"))
      (node (ref "MC2") (pin "12") (pinfunction "12_12") (pintype "passive"))
      (node (ref "MC2") (pin "17") (pinfunction "17_17") (pintype "passive"))
      (node (ref "MC2") (pin "18") (pinfunction "18_18") (pintype "passive"))
      (node (ref "MC2") (pin "5") (pinfunction "5_5") (pintype "passive"))
      (node (ref "MC2") (pin "53") (pinfunction "53_53") (pintype "passive"))
      (node (ref "MC2") (pin "54") (pinfunction "54_54") (pintype "passive"))
      (node (ref "MC2") (pin "6") (pinfunction "6_6") (pintype "passive"))
      (node (ref "MC2") (pin "65") (pinfunction "65_65") (pintype "passive"))
      (node (ref "MC2") (pin "66") (pinfunction "66_66") (pintype "passive"))
      (node (ref "MC2") (pin "71") (pinfunction "71_71") (pintype "passive"))
      (node (ref "MC2") (pin "72") (pinfunction "72_72") (pintype "passive"))
      (node (ref "MC2") (pin "77") (pinfunction "77_77") (pintype "passive"))
      (node (ref "MC2") (pin "78") (pinfunction "78_78") (pintype "passive"))
      (node (ref "MC2") (pin "83") (pinfunction "83_83") (pintype "passive"))
      (node (ref "MC2") (pin "84") (pinfunction "84_84") (pintype "passive"))
      (node (ref "MC2") (pin "89") (pinfunction "89_89") (pintype "passive"))
      (node (ref "R28") (pin "1") (pinfunction "1_1") (pintype "passive"))
    )
    (net (code "245") (name "MC1_VREF1") (class "Default")
      (node (ref "MC1") (pin "114") (pinfunction "114_114") (pintype "passive"))
    )
    (net (code "246") (name "MC2_VREF3") (class "Default")
      (node (ref "MC2") (pin "114") (pinfunction "114_114") (pintype "passive"))
    )
    (net (code "247") (name "VADJ1") (class "Default")
      (node (ref "MC1") (pin "119") (pinfunction "119_119") (pintype "passive"))
      (node (ref "MC1") (pin "120") (pinfunction "120_120") (pintype "passive"))
      (node (ref "MC1") (pin "59") (pinfunction "59_59") (pintype "passive"))
      (node (ref "MC1") (pin "60") (pinfunction "60_60") (pintype "passive"))
    )
    (net (code "248") (name "VADJ2") (class "Default")
      (node (ref "MC2") (pin "59") (pinfunction "59_59") (pintype "passive"))
      (node (ref "MC2") (pin "60") (pinfunction "60_60") (pintype "passive"))
    )
    (net (code "249") (name "VADJ3") (class "Default")
      (node (ref "MC2") (pin "119") (pinfunction "119_119") (pintype "passive"))
      (node (ref "MC2") (pin "120") (pinfunction "120_120") (pintype "passive"))
    )
    (net (code "250") (name "unconnected-(MC2-Pad130)") (class "Default")
      (node (ref "MC2") (pin "130") (pinfunction "130_130") (pintype "passive+no_connect"))
    )
    (net (code "251") (name "unconnected-(MC2-Pad132)") (class "Default")
      (node (ref "MC2") (pin "132") (pinfunction "132_132") (pintype "passive+no_connect"))
    )
    (net (code "252") (name "unconnected-(MC2-Pad134)") (class "Default")
      (node (ref "MC2") (pin "134") (pinfunction "134_134") (pintype "passive+no_connect"))
    )
    (net (code "253") (name "unconnected-(MC2-Pad136)") (class "Default")
      (node (ref "MC2") (pin "136") (pinfunction "136_136") (pintype "passive+no_connect"))
    )
    (net (code "254") (name "unconnected-(MC2-Pad137)") (class "Default")
      (node (ref "MC2") (pin "137") (pinfunction "137_137") (pintype "passive+no_connect"))
    )
    (net (code "255") (name "unconnected-(MC2-Pad138)") (class "Default")
      (node (ref "MC2") (pin "138") (pinfunction "138_138") (pintype "passive+no_connect"))
    )
    (net (code "256") (name "unconnected-(MC2-Pad139)") (class "Default")
      (node (ref "MC2") (pin "139") (pinfunction "139_139") (pintype "passive+no_connect"))
    )
    (net (code "257") (name "unconnected-(MC2-Pad140)") (class "Default")
      (node (ref "MC2") (pin "140") (pinfunction "140_140") (pintype "passive+no_connect"))
    )
    (net (code "258") (name "unconnected-(MC2-Pad141)") (class "Default")
      (node (ref "MC2") (pin "141") (pinfunction "141_141") (pintype "passive+no_connect"))
    )
    (net (code "259") (name "unconnected-(MC2-Pad142)") (class "Default")
      (node (ref "MC2") (pin "142") (pinfunction "142_142") (pintype "passive+no_connect"))
    )
    (net (code "260") (name "unconnected-(MC2-Pad143)") (class "Default")
      (node (ref "MC2") (pin "143") (pinfunction "143_143") (pintype "passive+no_connect"))
    )
    (net (code "261") (name "unconnected-(MC2-Pad144)") (class "Default")
      (node (ref "MC2") (pin "144") (pinfunction "144_144") (pintype "passive+no_connect"))
    )
    (net (code "262") (name "unconnected-(MC2-Pad145)") (class "Default")
      (node (ref "MC2") (pin "145") (pinfunction "145_145") (pintype "passive+no_connect"))
    )
    (net (code "263") (name "unconnected-(MC2-Pad146)") (class "Default")
      (node (ref "MC2") (pin "146") (pinfunction "146_146") (pintype "passive+no_connect"))
    )
    (net (code "264") (name "unconnected-(MC2-Pad150)") (class "Default")
      (node (ref "MC2") (pin "150") (pinfunction "150_150") (pintype "passive+no_connect"))
    )
    (net (code "265") (name "unconnected-(MC2-Pad151)") (class "Default")
      (node (ref "MC2") (pin "151") (pinfunction "151_151") (pintype "passive+no_connect"))
    )
    (net (code "266") (name "unconnected-(MC2-Pad152)") (class "Default")
      (node (ref "MC2") (pin "152") (pinfunction "152_152") (pintype "passive+no_connect"))
    )
    (net (code "267") (name "unconnected-(MC2-Pad153)") (class "Default")
      (node (ref "MC2") (pin "153") (pinfunction "153_153") (pintype "passive+no_connect"))
    )
    (net (code "268") (name "unconnected-(MC2-Pad154)") (class "Default")
      (node (ref "MC2") (pin "154") (pinfunction "154_154") (pintype "passive+no_connect"))
    )
    (net (code "269") (name "unconnected-(MC2-Pad155)") (class "Default")
      (node (ref "MC2") (pin "155") (pinfunction "155_155") (pintype "passive+no_connect"))
    )
    (net (code "270") (name "unconnected-(MC2-Pad156)") (class "Default")
      (node (ref "MC2") (pin "156") (pinfunction "156_156") (pintype "passive+no_connect"))
    )
    (net (code "271") (name "unconnected-(MC2-Pad157)") (class "Default")
      (node (ref "MC2") (pin "157") (pinfunction "157_157") (pintype "passive+no_connect"))
    )
    (net (code "272") (name "unconnected-(MC2-Pad158)") (class "Default")
      (node (ref "MC2") (pin "158") (pinfunction "158_158") (pintype "passive+no_connect"))
    )
    (net (code "273") (name "unconnected-(MC2-Pad159)") (class "Default")
      (node (ref "MC2") (pin "159") (pinfunction "159_159") (pintype "passive+no_connect"))
    )
    (net (code "274") (name "unconnected-(MC2-Pad160)") (class "Default")
      (node (ref "MC2") (pin "160") (pinfunction "160_160") (pintype "passive+no_connect"))
    )
    (net (code "275") (name "unconnected-(MC2-Pad161)") (class "Default")
      (node (ref "MC2") (pin "161") (pinfunction "161_161") (pintype "passive+no_connect"))
    )
    (net (code "276") (name "unconnected-(MC2-Pad162)") (class "Default")
      (node (ref "MC2") (pin "162") (pinfunction "162_162") (pintype "passive+no_connect"))
    )
    (net (code "277") (name "unconnected-(MC2-Pad163)") (class "Default")
      (node (ref "MC2") (pin "163") (pinfunction "163_163") (pintype "passive+no_connect"))
    )
    (net (code "278") (name "unconnected-(MC2-Pad164)") (class "Default")
      (node (ref "MC2") (pin "164") (pinfunction "164_164") (pintype "passive+no_connect"))
    )
    (net (code "279") (name "unconnected-(MC2-Pad165)") (class "Default")
      (node (ref "MC2") (pin "165") (pinfunction "165_165") (pintype "passive+no_connect"))
    )
    (net (code "280") (name "unconnected-(MC2-Pad166)") (class "Default")
      (node (ref "MC2") (pin "166") (pinfunction "166_166") (pintype "passive+no_connect"))
    )
    (net (code "281") (name "unconnected-(MC2-Pad167)") (class "Default")
      (node (ref "MC2") (pin "167") (pinfunction "167_167") (pintype "passive+no_connect"))
    )
    (net (code "282") (name "unconnected-(MC2-Pad168)") (class "Default")
      (node (ref "MC2") (pin "168") (pinfunction "168_168") (pintype "passive+no_connect"))
    )
    (net (code "283") (name "unconnected-(MC2-Pad169)") (class "Default")
      (node (ref "MC2") (pin "169") (pinfunction "169_169") (pintype "passive+no_connect"))
    )
    (net (code "284") (name "unconnected-(MC2-Pad171)") (class "Default")
      (node (ref "MC2") (pin "171") (pinfunction "171_171") (pintype "passive+no_connect"))
    )
    (net (code "285") (name "unconnected-(MC2-Pad173)") (class "Default")
      (node (ref "MC2") (pin "173") (pinfunction "173_173") (pintype "passive+no_connect"))
    )
  )
)
